# Customer_Module-APS_Connector.net
KiCad netlist of a schematic drawn in Altium Designer
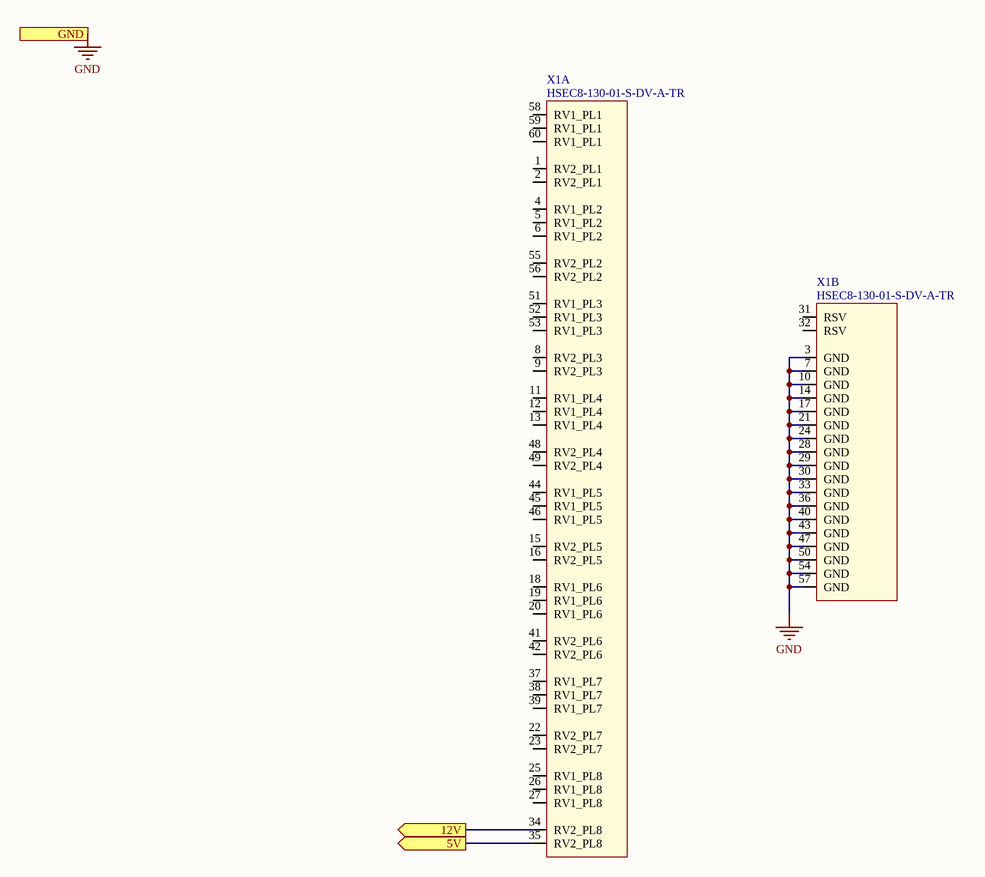
[diagram p0: Customer_Module-APS_Connector.SchDoc]

(export (version "E")
  (design (tool "Eeschema 10.0.6"))
  (components
    (comp (ref "X1")
      (value "HSEC8-130-01-S-DV-A-TR")
      (footprint "HSEC8-130-01-S-DV-A-TR")
      (libsource (lib "HSEC8-130-01-S-DV-A-TR") (part "HSEC8-130-01-S-DV-A-TR"))
    )
  )
  (nets
    (net (code "1") (name "/5V") (class "Default")
      (node (ref "X1") (pin "35") (pinfunction "RV2_PL8_35") (pintype "passive"))
    )
    (net (code "2") (name "/12V") (class "Default")
      (node (ref "X1") (pin "34") (pinfunction "RV2_PL8_34") (pintype "passive"))
    )
    (net (code "3") (name "GND") (class "Default")
      (node (ref "X1") (pin "10") (pinfunction "GND_10") (pintype "passive"))
      (node (ref "X1") (pin "14") (pinfunction "GND_14") (pintype "passive"))
      (node (ref "X1") (pin "17") (pinfunction "GND_17") (pintype "passive"))
      (node (ref "X1") (pin "21") (pinfunction "GND_21") (pintype "passive"))
      (node (ref "X1") (pin "24") (pinfunction "GND_24") (pintype "passive"))
      (node (ref "X1") (pin "28") (pinfunction "GND_28") (pintype "passive"))
      (node (ref "X1") (pin "29") (pinfunction "GND_29") (pintype "passive"))
      (node (ref "X1") (pin "3") (pinfunction "GND_3") (pintype "passive"))
      (node (ref "X1") (pin "30") (pinfunction "GND_30") (pintype "passive"))
      (node (ref "X1") (pin "33") (pinfunction "GND_33") (pintype "passive"))
      (node (ref "X1") (pin "36") (pinfunction "GND_36") (pintype "passive"))
      (node (ref "X1") (pin "40") (pinfunction "GND_40") (pintype "passive"))
      (node (ref "X1") (pin "43") (pinfunction "GND_43") (pintype "passive"))
      (node (ref "X1") (pin "47") (pinfunction "GND_47") (pintype "passive"))
      (node (ref "X1") (pin "50") (pinfunction "GND_50") (pintype "passive"))
      (node (ref "X1") (pin "54") (pinfunction "GND_54") (pintype "passive"))
      (node (ref "X1") (pin "57") (pinfunction "GND_57") (pintype "passive"))
      (node (ref "X1") (pin "7") (pinfunction "GND_7") (pintype "passive"))
    )
    (net (code "4") (name "unconnected-(X1A-RV1_PL1-Pad58)") (class "Default")
      (node (ref "X1") (pin "58") (pinfunction "RV1_PL1_58") (pintype "passive"))
    )
    (net (code "5") (name "unconnected-(X1A-RV1_PL1-Pad59)") (class "Default")
      (node (ref "X1") (pin "59") (pinfunction "RV1_PL1_59") (pintype "passive"))
    )
    (net (code "6") (name "unconnected-(X1A-RV1_PL1-Pad60)") (class "Default")
      (node (ref "X1") (pin "60") (pinfunction "RV1_PL1_60") (pintype "passive"))
    )
    (net (code "7") (name "unconnected-(X1A-RV1_PL2-Pad4)") (class "Default")
      (node (ref "X1") (pin "4") (pinfunction "RV1_PL2_4") (pintype "passive"))
    )
    (net (code "8") (name "unconnected-(X1A-RV1_PL2-Pad5)") (class "Default")
      (node (ref "X1") (pin "5") (pinfunction "RV1_PL2_5") (pintype "passive"))
    )
    (net (code "9") (name "unconnected-(X1A-RV1_PL2-Pad6)") (class "Default")
      (node (ref "X1") (pin "6") (pinfunction "RV1_PL2_6") (pintype "passive"))
    )
    (net (code "10") (name "unconnected-(X1A-RV1_PL3-Pad51)") (class "Default")
      (node (ref "X1") (pin "51") (pinfunction "RV1_PL3_51") (pintype "passive"))
    )
    (net (code "11") (name "unconnected-(X1A-RV1_PL3-Pad52)") (class "Default")
      (node (ref "X1") (pin "52") (pinfunction "RV1_PL3_52") (pintype "passive"))
    )
    (net (code "12") (name "unconnected-(X1A-RV1_PL3-Pad53)") (class "Default")
      (node (ref "X1") (pin "53") (pinfunction "RV1_PL3_53") (pintype "passive"))
    )
    (net (code "13") (name "unconnected-(X1A-RV1_PL4-Pad11)") (class "Default")
      (node (ref "X1") (pin "11") (pinfunction "RV1_PL4_11") (pintype "passive"))
    )
    (net (code "14") (name "unconnected-(X1A-RV1_PL4-Pad12)") (class "Default")
      (node (ref "X1") (pin "12") (pinfunction "RV1_PL4_12") (pintype "passive"))
    )
    (net (code "15") (name "unconnected-(X1A-RV1_PL4-Pad13)") (class "Default")
      (node (ref "X1") (pin "13") (pinfunction "RV1_PL4_13") (pintype "passive"))
    )
    (net (code "16") (name "unconnected-(X1A-RV1_PL5-Pad44)") (class "Default")
      (node (ref "X1") (pin "44") (pinfunction "RV1_PL5_44") (pintype "passive"))
    )
    (net (code "17") (name "unconnected-(X1A-RV1_PL5-Pad45)") (class "Default")
      (node (ref "X1") (pin "45") (pinfunction "RV1_PL5_45") (pintype "passive"))
    )
    (net (code "18") (name "unconnected-(X1A-RV1_PL5-Pad46)") (class "Default")
      (node (ref "X1") (pin "46") (pinfunction "RV1_PL5_46") (pintype "passive"))
    )
    (net (code "19") (name "unconnected-(X1A-RV1_PL6-Pad18)") (class "Default")
      (node (ref "X1") (pin "18") (pinfunction "RV1_PL6_18") (pintype "passive"))
    )
    (net (code "20") (name "unconnected-(X1A-RV1_PL6-Pad19)") (class "Default")
      (node (ref "X1") (pin "19") (pinfunction "RV1_PL6_19") (pintype "passive"))
    )
    (net (code "21") (name "unconnected-(X1A-RV1_PL6-Pad20)") (class "Default")
      (node (ref "X1") (pin "20") (pinfunction "RV1_PL6_20") (pintype "passive"))
    )
    (net (code "22") (name "unconnected-(X1A-RV1_PL7-Pad37)") (class "Default")
      (node (ref "X1") (pin "37") (pinfunction "RV1_PL7_37") (pintype "passive"))
    )
    (net (code "23") (name "unconnected-(X1A-RV1_PL7-Pad38)") (class "Default")
      (node (ref "X1") (pin "38") (pinfunction "RV1_PL7_38") (pintype "passive"))
    )
    (net (code "24") (name "unconnected-(X1A-RV1_PL7-Pad39)") (class "Default")
      (node (ref "X1") (pin "39") (pinfunction "RV1_PL7_39") (pintype "passive"))
    )
    (net (code "25") (name "unconnected-(X1A-RV1_PL8-Pad25)") (class "Default")
      (node (ref "X1") (pin "25") (pinfunction "RV1_PL8_25") (pintype "passive"))
    )
    (net (code "26") (name "unconnected-(X1A-RV1_PL8-Pad26)") (class "Default")
      (node (ref "X1") (pin "26") (pinfunction "RV1_PL8_26") (pintype "passive"))
    )
    (net (code "27") (name "unconnected-(X1A-RV1_PL8-Pad27)") (class "Default")
      (node (ref "X1") (pin "27") (pinfunction "RV1_PL8_27") (pintype "passive"))
    )
    (net (code "28") (name "unconnected-(X1A-RV2_PL1-Pad1)") (class "Default")
      (node (ref "X1") (pin "1") (pinfunction "RV2_PL1_1") (pintype "passive"))
    )
    (net (code "29") (name "unconnected-(X1A-RV2_PL1-Pad2)") (class "Default")
      (node (ref "X1") (pin "2") (pinfunction "RV2_PL1_2") (pintype "passive"))
    )
    (net (code "30") (name "unconnected-(X1A-RV2_PL2-Pad55)") (class "Default")
      (node (ref "X1") (pin "55") (pinfunction "RV2_PL2_55") (pintype "passive"))
    )
    (net (code "31") (name "unconnected-(X1A-RV2_PL2-Pad56)") (class "Default")
      (node (ref "X1") (pin "56") (pinfunction "RV2_PL2_56") (pintype "passive"))
    )
    (net (code "32") (name "unconnected-(X1A-RV2_PL3-Pad8)") (class "Default")
      (node (ref "X1") (pin "8") (pinfunction "RV2_PL3_8") (pintype "passive"))
    )
    (net (code "33") (name "unconnected-(X1A-RV2_PL3-Pad9)") (class "Default")
      (node (ref "X1") (pin "9") (pinfunction "RV2_PL3_9") (pintype "passive"))
    )
    (net (code "34") (name "unconnected-(X1A-RV2_PL4-Pad48)") (class "Default")
      (node (ref "X1") (pin "48") (pinfunction "RV2_PL4_48") (pintype "passive"))
    )
    (net (code "35") (name "unconnected-(X1A-RV2_PL4-Pad49)") (class "Default")
      (node (ref "X1") (pin "49") (pinfunction "RV2_PL4_49") (pintype "passive"))
    )
    (net (code "36") (name "unconnected-(X1A-RV2_PL5-Pad15)") (class "Default")
      (node (ref "X1") (pin "15") (pinfunction "RV2_PL5_15") (pintype "passive"))
    )
    (net (code "37") (name "unconnected-(X1A-RV2_PL5-Pad16)") (class "Default")
      (node (ref "X1") (pin "16") (pinfunction "RV2_PL5_16") (pintype "passive"))
    )
    (net (code "38") (name "unconnected-(X1A-RV2_PL6-Pad41)") (class "Default")
      (node (ref "X1") (pin "41") (pinfunction "RV2_PL6_41") (pintype "passive"))
    )
    (net (code "39") (name "unconnected-(X1A-RV2_PL6-Pad42)") (class "Default")
      (node (ref "X1") (pin "42") (pinfunction "RV2_PL6_42") (pintype "passive"))
    )
    (net (code "40") (name "unconnected-(X1A-RV2_PL7-Pad22)") (class "Default")
      (node (ref "X1") (pin "22") (pinfunction "RV2_PL7_22") (pintype "passive"))
    )
    (net (code "41") (name "unconnected-(X1A-RV2_PL7-Pad23)") (class "Default")
      (node (ref "X1") (pin "23") (pinfunction "RV2_PL7_23") (pintype "passive"))
    )
    (net (code "42") (name "unconnected-(X1B-RSV-Pad31)") (class "Default")
      (node (ref "X1") (pin "31") (pinfunction "RSV_31") (pintype "passive"))
    )
    (net (code "43") (name "unconnected-(X1B-RSV-Pad32)") (class "Default")
      (node (ref "X1") (pin "32") (pinfunction "RSV_32") (pintype "passive"))
    )
  )
)
